# 01_MCU.net
KiCad netlist of a schematic drawn in Altium Designer
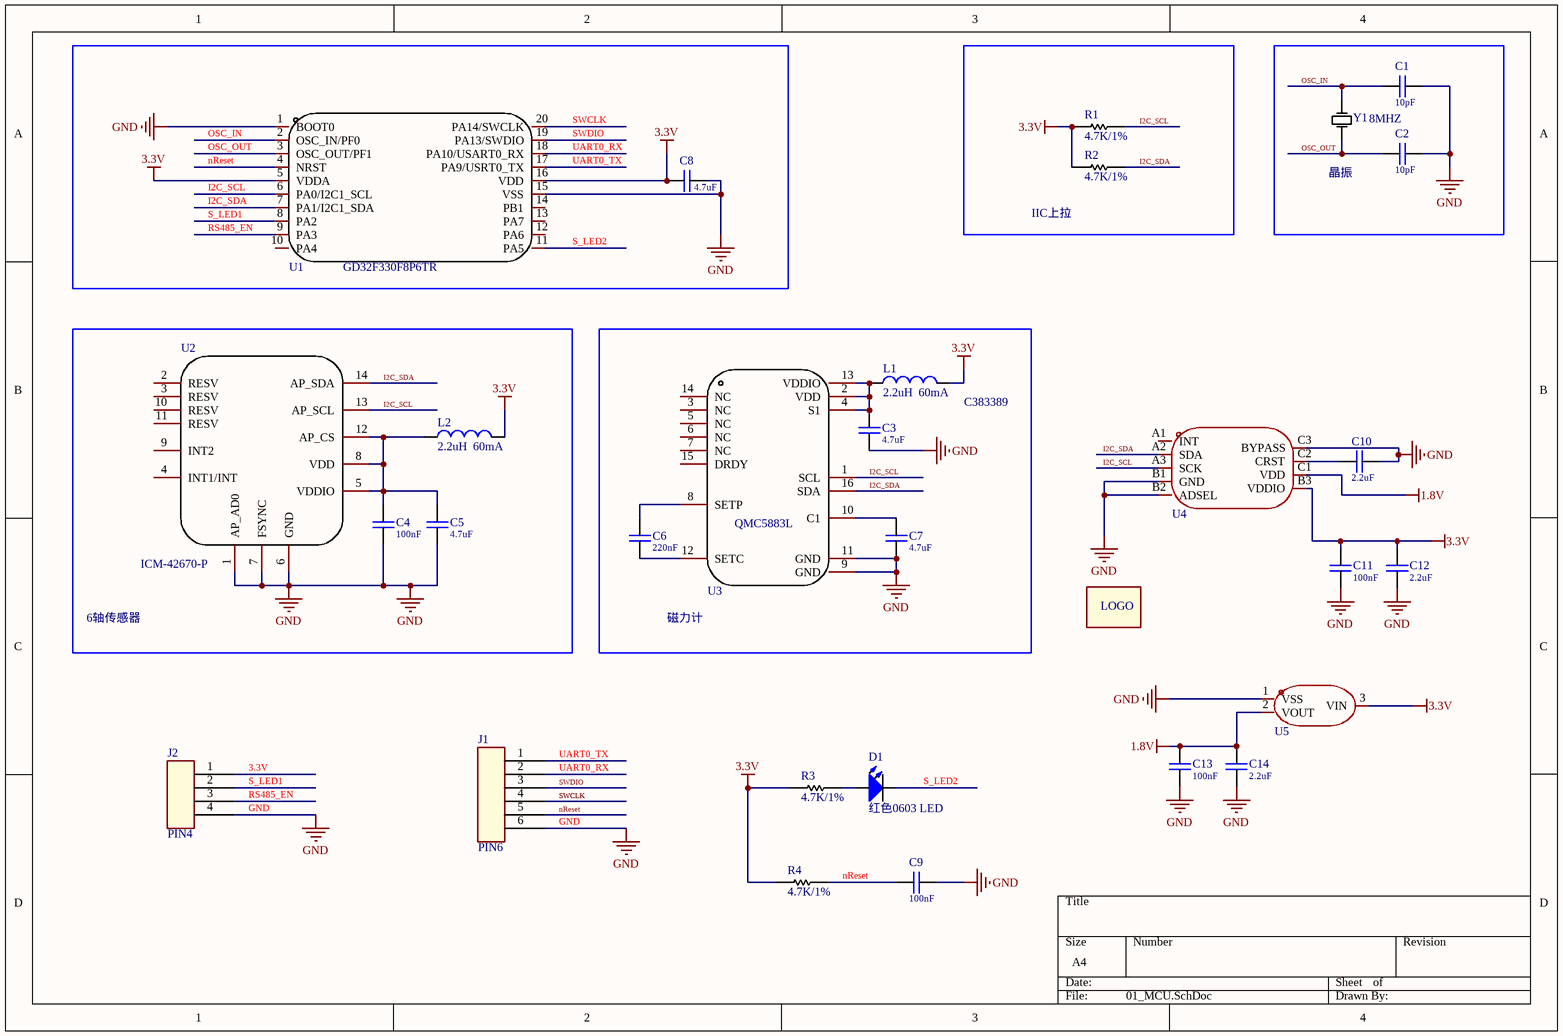
[diagram p0: 01_MCU.SchDoc]

(export (version "E")
  (design (tool "Eeschema 10.0.6"))
  (components
    (comp (ref "C1")
      (value "10pF")
      (footprint "C0402_M")
      (libsource (lib "AOT4G_MAINBOARD_Library") (part "CAP_0402"))
    )
    (comp (ref "C2")
      (value "10pF")
      (footprint "C0402_M")
      (libsource (lib "AOT4G_MAINBOARD_Library") (part "CAP_0402"))
    )
    (comp (ref "C3")
      (value "4.7uF")
      (footprint "0603C2")
      (libsource (lib "AOT4G_MAINBOARD_Library") (part "CAP"))
    )
    (comp (ref "C4")
      (value "100nF")
      (footprint "C0402_M")
      (libsource (lib "AOT4G_MAINBOARD_Library") (part "CAP_0402"))
    )
    (comp (ref "C5")
      (value "4.7uF")
      (footprint "0603C2")
      (libsource (lib "AOT4G_MAINBOARD_Library") (part "CAP"))
    )
    (comp (ref "C6")
      (value "220nF")
      (footprint "C0402_M")
      (libsource (lib "AOT4G_MAINBOARD_Library") (part "CAP_0402"))
    )
    (comp (ref "C7")
      (value "4.7uF")
      (footprint "0603C2")
      (libsource (lib "AOT4G_MAINBOARD_Library") (part "CAP"))
    )
    (comp (ref "C8")
      (value "4.7uF")
      (footprint "0603C2")
      (libsource (lib "AOT4G_MAINBOARD_Library") (part "CAP"))
    )
    (comp (ref "C9")
      (value "100nF")
      (footprint "C0402_M")
      (libsource (lib "AOT4G_MAINBOARD_Library") (part "CAP_0402"))
    )
    (comp (ref "C10")
      (value "2.2uF")
      (footprint "0603C2")
      (libsource (lib "AOT4G_MAINBOARD_Library") (part "CAP"))
    )
    (comp (ref "C11")
      (value "100nF")
      (footprint "C0402_M")
      (libsource (lib "AOT4G_MAINBOARD_Library") (part "CAP_0402"))
    )
    (comp (ref "C12")
      (value "2.2uF")
      (footprint "0603C2")
      (libsource (lib "AOT4G_MAINBOARD_Library") (part "CAP"))
    )
    (comp (ref "C13")
      (value "100nF")
      (footprint "C0402_M")
      (libsource (lib "AOT4G_MAINBOARD_Library") (part "CAP_0402"))
    )
    (comp (ref "C14")
      (value "2.2uF")
      (footprint "0603C2")
      (libsource (lib "AOT4G_MAINBOARD_Library") (part "CAP"))
    )
    (comp (ref "D1")
      (value "红色0603 LED")
      (footprint "0603_LED_S1")
      (libsource (lib "AOT4G_MAINBOARD_Library") (part "LED"))
    )
    (comp (ref "J1")
      (value "PIN6")
      (footprint "HDR2.54-LI-6P")
      (libsource (lib "AOT4G_MAINBOARD_Library") (part "PIN6"))
    )
    (comp (ref "J2")
      (value "PIN4")
      (footprint "HDR2.54-LI-4P")
      (libsource (lib "AOT4G_MAINBOARD_Library") (part "PIN4"))
    )
    (comp (ref "L1")
      (value "2.2uH  60mA")
      (footprint "L0402")
      (description "MLZ1005M2R2WT000   60mA")
      (libsource (lib "AOT4G_MAINBOARD_Library") (part "INDUCTOR_0402"))
    )
    (comp (ref "L2")
      (value "2.2uH  60mA")
      (footprint "L0402")
      (description "MLZ1005M2R2WT000   60mA")
      (libsource (lib "AOT4G_MAINBOARD_Library") (part "INDUCTOR_0402"))
    )
    (comp (ref "logo1")
      (value "JJ_LOGO")
      (footprint "JJ-LOGO")
      (libsource (lib "AOT4G_MAINBOARD_Library") (part "JJ_LOGO"))
    )
    (comp (ref "R1")
      (value "4.7K/1%")
      (footprint "R0402_M")
      (libsource (lib "AOT4G_MAINBOARD_Library") (part "RES-0402"))
    )
    (comp (ref "R2")
      (value "4.7K/1%")
      (footprint "R0402_M")
      (libsource (lib "AOT4G_MAINBOARD_Library") (part "RES-0402"))
    )
    (comp (ref "R3")
      (value "4.7K/1%")
      (footprint "R0402_M")
      (libsource (lib "AOT4G_MAINBOARD_Library") (part "RES-0402"))
    )
    (comp (ref "R4")
      (value "4.7K/1%")
      (footprint "R0402_M")
      (libsource (lib "AOT4G_MAINBOARD_Library") (part "RES-0402"))
    )
    (comp (ref "U1")
      (value "GD32F330F8P6TR")
      (footprint "TSSOP-20_L6.5-W4.4-P0.65-LS6.4-BL")
      (description "CPU内核:CM4;程序存储容量:64KB;RAM总容量:8KB;GPIO端口数量:15;工作电压范围:2.6V~3.6V;CPU最大主频:84MHz;程序存储器类型:FLASH;")
      (fields (field (name "MANUFACTURER") "GigaDevice(兆易创新)"))
      (libsource (lib "AOT4G_MAINBOARD_Library") (part "GD32F330F8P6TR"))
    )
    (comp (ref "U2")
      (value "ICM-42670-P")
      (footprint "LGA-14_2.5X3.0")
      (description "6-axis")
      (libsource (lib "AOT4G_MAINBOARD_Library") (part "ICM-42670-P"))
    )
    (comp (ref "U3")
      (value "QMC5883L")
      (footprint "LGA-16_L3.0-W3.0-P0.50-BL_SQ")
      (fields (field (name "MANUFACTURER") "QST(上海矽睿)"))
      (libsource (lib "AOT4G_MAINBOARD_Library") (part "QMC5883L"))
    )
    (comp (ref "U4")
      (value "BMM350")
      (footprint "WLCSP-9_L1.3-W1.3-R3-C3-P0.40-TL")
      (fields (field (name "MANUFACTURER") "Bosch(博世)"))
      (libsource (lib "AOT4G_MAINBOARD_Library") (part "BMM350_C17225907"))
    )
    (comp (ref "U5")
      (value "XC6206P182MR")
      (footprint "SOT-23-3_L2.9-W1.6-P1.90-LS2.8-BR")
      (fields (field (name "MANUFACTURER") "UMW(友台半导体)"))
      (libsource (lib "AOT4G_MAINBOARD_Library") (part "XC6206P182MR_C347373"))
    )
    (comp (ref "Y1")
      (value "8MHZ")
      (footprint "OSC-5032-2P")
      (description "CR5032  8MHZ")
      (libsource (lib "AOT4G_MAINBOARD_Library") (part "8MHZ"))
    )
  )
  (nets
    (net (code "1") (name "/I2C_SCL") (class "Default")
      (node (ref "R1") (pin "1") (pinfunction "1_1") (pintype "passive"))
      (node (ref "U1") (pin "6") (pinfunction "PA0/I2C1_SCL_6") (pintype "passive"))
      (node (ref "U2") (pin "13") (pinfunction "AP_SCL_13") (pintype "passive"))
      (node (ref "U3") (pin "1") (pinfunction "SCL_1") (pintype "passive"))
      (node (ref "U4") (pin "A3") (pinfunction "SCK_A3") (pintype "passive"))
    )
    (net (code "2") (name "/I2C_SDA") (class "Default")
      (node (ref "R2") (pin "1") (pinfunction "1_1") (pintype "passive"))
      (node (ref "U1") (pin "7") (pinfunction "PA1/I2C1_SDA_7") (pintype "passive"))
      (node (ref "U2") (pin "14") (pinfunction "AP_SDA_14") (pintype "passive"))
      (node (ref "U3") (pin "16") (pinfunction "SDA_16") (pintype "passive"))
      (node (ref "U4") (pin "A2") (pinfunction "SDA_A2") (pintype "passive"))
    )
    (net (code "3") (name "/OSC_IN") (class "Default")
      (node (ref "C1") (pin "1") (pinfunction "1_1") (pintype "passive"))
      (node (ref "U1") (pin "2") (pinfunction "OSC_IN/PF0_2") (pintype "passive"))
      (node (ref "Y1") (pin "2") (pinfunction "OSC2_2") (pintype "passive"))
    )
    (net (code "4") (name "/OSC_OUT") (class "Default")
      (node (ref "C2") (pin "1") (pinfunction "1_1") (pintype "passive"))
      (node (ref "U1") (pin "3") (pinfunction "OSC_OUT/PF1_3") (pintype "passive"))
      (node (ref "Y1") (pin "1") (pinfunction "OSC1_1") (pintype "passive"))
    )
    (net (code "5") (name "/RS485_EN") (class "Default")
      (node (ref "J2") (pin "3") (pinfunction "3_3") (pintype "passive"))
      (node (ref "U1") (pin "9") (pinfunction "PA3_9") (pintype "passive"))
    )
    (net (code "6") (name "/SWCLK") (class "Default")
      (node (ref "J1") (pin "4") (pinfunction "4_4") (pintype "passive"))
      (node (ref "U1") (pin "20") (pinfunction "PA14/SWCLK_20") (pintype "passive"))
    )
    (net (code "7") (name "/SWDIO") (class "Default")
      (node (ref "J1") (pin "3") (pinfunction "3_3") (pintype "passive"))
      (node (ref "U1") (pin "19") (pinfunction "PA13/SWDIO_19") (pintype "passive"))
    )
    (net (code "8") (name "/S_LED1") (class "Default")
      (node (ref "J2") (pin "2") (pinfunction "2_2") (pintype "passive"))
      (node (ref "U1") (pin "8") (pinfunction "PA2_8") (pintype "passive"))
    )
    (net (code "9") (name "/S_LED2") (class "Default")
      (node (ref "D1") (pin "2") (pinfunction "K_2") (pintype "passive"))
      (node (ref "U1") (pin "11") (pinfunction "PA5_11") (pintype "passive"))
    )
    (net (code "10") (name "/UART0_RX") (class "Default")
      (node (ref "J1") (pin "2") (pinfunction "2_2") (pintype "passive"))
      (node (ref "U1") (pin "18") (pinfunction "PA10/USART0_RX_18") (pintype "passive"))
    )
    (net (code "11") (name "/UART0_TX") (class "Default")
      (node (ref "J1") (pin "1") (pinfunction "1_1") (pintype "passive"))
      (node (ref "U1") (pin "17") (pinfunction "PA9/USRT0_TX_17") (pintype "passive"))
    )
    (net (code "12") (name "/nReset") (class "Default")
      (node (ref "C9") (pin "1") (pinfunction "1_1") (pintype "passive"))
      (node (ref "J1") (pin "5") (pinfunction "5_5") (pintype "passive"))
      (node (ref "R4") (pin "1") (pinfunction "1_1") (pintype "passive"))
      (node (ref "U1") (pin "4") (pinfunction "NRST_4") (pintype "passive"))
    )
    (net (code "13") (name "1.8V") (class "Default")
      (node (ref "C13") (pin "2") (pinfunction "2_2") (pintype "passive"))
      (node (ref "C14") (pin "1") (pinfunction "1_1") (pintype "passive"))
      (node (ref "U4") (pin "C1") (pinfunction "VDD_C1") (pintype "passive"))
      (node (ref "U5") (pin "2") (pinfunction "VOUT_2") (pintype "passive"))
    )
    (net (code "14") (name "3.3V") (class "Default")
      (node (ref "C11") (pin "2") (pinfunction "2_2") (pintype "passive"))
      (node (ref "C12") (pin "1") (pinfunction "1_1") (pintype "passive"))
      (node (ref "C8") (pin "1") (pinfunction "1_1") (pintype "passive"))
      (node (ref "J2") (pin "1") (pinfunction "1_1") (pintype "passive"))
      (node (ref "L1") (pin "2") (pinfunction "2_2") (pintype "passive"))
      (node (ref "L2") (pin "2") (pinfunction "2_2") (pintype "passive"))
      (node (ref "R1") (pin "2") (pinfunction "2_2") (pintype "passive"))
      (node (ref "R2") (pin "2") (pinfunction "2_2") (pintype "passive"))
      (node (ref "R3") (pin "2") (pinfunction "2_2") (pintype "passive"))
      (node (ref "R4") (pin "2") (pinfunction "2_2") (pintype "passive"))
      (node (ref "U1") (pin "16") (pinfunction "VDD_16") (pintype "passive"))
      (node (ref "U1") (pin "5") (pinfunction "VDDA_5") (pintype "passive"))
      (node (ref "U4") (pin "B3") (pinfunction "VDDIO_B3") (pintype "passive"))
      (node (ref "U5") (pin "3") (pinfunction "VIN_3") (pintype "passive"))
    )
    (net (code "15") (name "GND") (class "Default")
      (node (ref "C1") (pin "2") (pinfunction "2_2") (pintype "passive"))
      (node (ref "C10") (pin "1") (pinfunction "1_1") (pintype "passive"))
      (node (ref "C11") (pin "1") (pinfunction "1_1") (pintype "passive"))
      (node (ref "C12") (pin "2") (pinfunction "2_2") (pintype "passive"))
      (node (ref "C13") (pin "1") (pinfunction "1_1") (pintype "passive"))
      (node (ref "C14") (pin "2") (pinfunction "2_2") (pintype "passive"))
      (node (ref "C2") (pin "2") (pinfunction "2_2") (pintype "passive"))
      (node (ref "C3") (pin "1") (pinfunction "1_1") (pintype "passive"))
      (node (ref "C4") (pin "1") (pinfunction "1_1") (pintype "passive"))
      (node (ref "C5") (pin "2") (pinfunction "2_2") (pintype "passive"))
      (node (ref "C7") (pin "2") (pinfunction "2_2") (pintype "passive"))
      (node (ref "C8") (pin "2") (pinfunction "2_2") (pintype "passive"))
      (node (ref "C9") (pin "2") (pinfunction "2_2") (pintype "passive"))
      (node (ref "J1") (pin "6") (pinfunction "6_6") (pintype "passive"))
      (node (ref "J2") (pin "4") (pinfunction "4_4") (pintype "passive"))
      (node (ref "U1") (pin "1") (pinfunction "BOOT0_1") (pintype "passive"))
      (node (ref "U1") (pin "15") (pinfunction "VSS_15") (pintype "passive"))
      (node (ref "U2") (pin "1") (pinfunction "AP_AD0_1") (pintype "passive"))
      (node (ref "U2") (pin "6") (pinfunction "GND_6") (pintype "passive"))
      (node (ref "U2") (pin "7") (pinfunction "FSYNC_7") (pintype "passive"))
      (node (ref "U3") (pin "11") (pinfunction "GND_11") (pintype "passive"))
      (node (ref "U3") (pin "9") (pinfunction "GND_9") (pintype "passive"))
      (node (ref "U4") (pin "B1") (pinfunction "GND_B1") (pintype "passive"))
      (node (ref "U4") (pin "B2") (pinfunction "ADSEL_B2") (pintype "passive"))
      (node (ref "U4") (pin "C3") (pinfunction "BYPASS_C3") (pintype "passive"))
      (node (ref "U5") (pin "1") (pinfunction "VSS_1") (pintype "passive"))
    )
    (net (code "16") (name "Net-(D1-A)") (class "Default")
      (node (ref "D1") (pin "1") (pinfunction "A_1") (pintype "passive"))
      (node (ref "R3") (pin "1") (pinfunction "1_1") (pintype "passive"))
    )
    (net (code "17") (name "Net-(U2-AP_CS)") (class "Default")
      (node (ref "C4") (pin "2") (pinfunction "2_2") (pintype "passive"))
      (node (ref "C5") (pin "1") (pinfunction "1_1") (pintype "passive"))
      (node (ref "L2") (pin "1") (pinfunction "1_1") (pintype "passive"))
      (node (ref "U2") (pin "12") (pinfunction "AP_CS_12") (pintype "passive"))
      (node (ref "U2") (pin "5") (pinfunction "VDDIO_5") (pintype "passive"))
      (node (ref "U2") (pin "8") (pinfunction "VDD_8") (pintype "passive"))
    )
    (net (code "18") (name "Net-(U3-C1)") (class "Default")
      (node (ref "C7") (pin "1") (pinfunction "1_1") (pintype "passive"))
      (node (ref "U3") (pin "10") (pinfunction "C1_10") (pintype "passive"))
    )
    (net (code "19") (name "Net-(U3-S1)") (class "Default")
      (node (ref "C3") (pin "2") (pinfunction "2_2") (pintype "passive"))
      (node (ref "L1") (pin "1") (pinfunction "1_1") (pintype "passive"))
      (node (ref "U3") (pin "13") (pinfunction "VDDIO_13") (pintype "passive"))
      (node (ref "U3") (pin "2") (pinfunction "VDD_2") (pintype "passive"))
      (node (ref "U3") (pin "4") (pinfunction "S1_4") (pintype "passive"))
    )
    (net (code "20") (name "Net-(U3-SETC)") (class "Default")
      (node (ref "C6") (pin "1") (pinfunction "1_1") (pintype "passive"))
      (node (ref "U3") (pin "12") (pinfunction "SETC_12") (pintype "passive"))
    )
    (net (code "21") (name "Net-(U3-SETP)") (class "Default")
      (node (ref "C6") (pin "2") (pinfunction "2_2") (pintype "passive"))
      (node (ref "U3") (pin "8") (pinfunction "SETP_8") (pintype "passive"))
    )
    (net (code "22") (name "Net-(U4-CRST)") (class "Default")
      (node (ref "C10") (pin "2") (pinfunction "2_2") (pintype "passive"))
      (node (ref "U4") (pin "C2") (pinfunction "CRST_C2") (pintype "passive"))
    )
    (net (code "23") (name "unconnected-(U1-PA4-Pad10)") (class "Default")
      (node (ref "U1") (pin "10") (pinfunction "PA4_10") (pintype "passive"))
    )
    (net (code "24") (name "unconnected-(U1-PA6-Pad12)") (class "Default")
      (node (ref "U1") (pin "12") (pinfunction "PA6_12") (pintype "passive"))
    )
    (net (code "25") (name "unconnected-(U1-PA7-Pad13)") (class "Default")
      (node (ref "U1") (pin "13") (pinfunction "PA7_13") (pintype "passive"))
    )
    (net (code "26") (name "unconnected-(U1-PB1-Pad14)") (class "Default")
      (node (ref "U1") (pin "14") (pinfunction "PB1_14") (pintype "passive"))
    )
    (net (code "27") (name "unconnected-(U2-INT1{slash}INT-Pad4)") (class "Default")
      (node (ref "U2") (pin "4") (pinfunction "INT1/INT_4") (pintype "passive"))
    )
    (net (code "28") (name "unconnected-(U2-INT2-Pad9)") (class "Default")
      (node (ref "U2") (pin "9") (pinfunction "INT2_9") (pintype "passive"))
    )
    (net (code "29") (name "unconnected-(U2-RESV-Pad2)") (class "Default")
      (node (ref "U2") (pin "2") (pinfunction "RESV_2") (pintype "passive"))
    )
    (net (code "30") (name "unconnected-(U2-RESV-Pad3)") (class "Default")
      (node (ref "U2") (pin "3") (pinfunction "RESV_3") (pintype "passive"))
    )
    (net (code "31") (name "unconnected-(U2-RESV-Pad10)") (class "Default")
      (node (ref "U2") (pin "10") (pinfunction "RESV_10") (pintype "passive"))
    )
    (net (code "32") (name "unconnected-(U2-RESV-Pad11)") (class "Default")
      (node (ref "U2") (pin "11") (pinfunction "RESV_11") (pintype "passive"))
    )
    (net (code "33") (name "unconnected-(U3-DRDY-Pad15)") (class "Default")
      (node (ref "U3") (pin "15") (pinfunction "DRDY_15") (pintype "passive"))
    )
    (net (code "34") (name "unconnected-(U3-NC-Pad3)") (class "Default")
      (node (ref "U3") (pin "3") (pinfunction "NC_3") (pintype "passive"))
    )
    (net (code "35") (name "unconnected-(U3-NC-Pad5)") (class "Default")
      (node (ref "U3") (pin "5") (pinfunction "NC_5") (pintype "passive"))
    )
    (net (code "36") (name "unconnected-(U3-NC-Pad6)") (class "Default")
      (node (ref "U3") (pin "6") (pinfunction "NC_6") (pintype "passive"))
    )
    (net (code "37") (name "unconnected-(U3-NC-Pad7)") (class "Default")
      (node (ref "U3") (pin "7") (pinfunction "NC_7") (pintype "passive"))
    )
    (net (code "38") (name "unconnected-(U3-NC-Pad14)") (class "Default")
      (node (ref "U3") (pin "14") (pinfunction "NC_14") (pintype "passive"))
    )
    (net (code "39") (name "unconnected-(U4-INT-PadA1)") (class "Default")
      (node (ref "U4") (pin "A1") (pinfunction "INT_A1") (pintype "passive"))
    )
  )
)
